# FPGA_DDR3_IO.net
KiCad netlist of a schematic drawn in Altium Designer
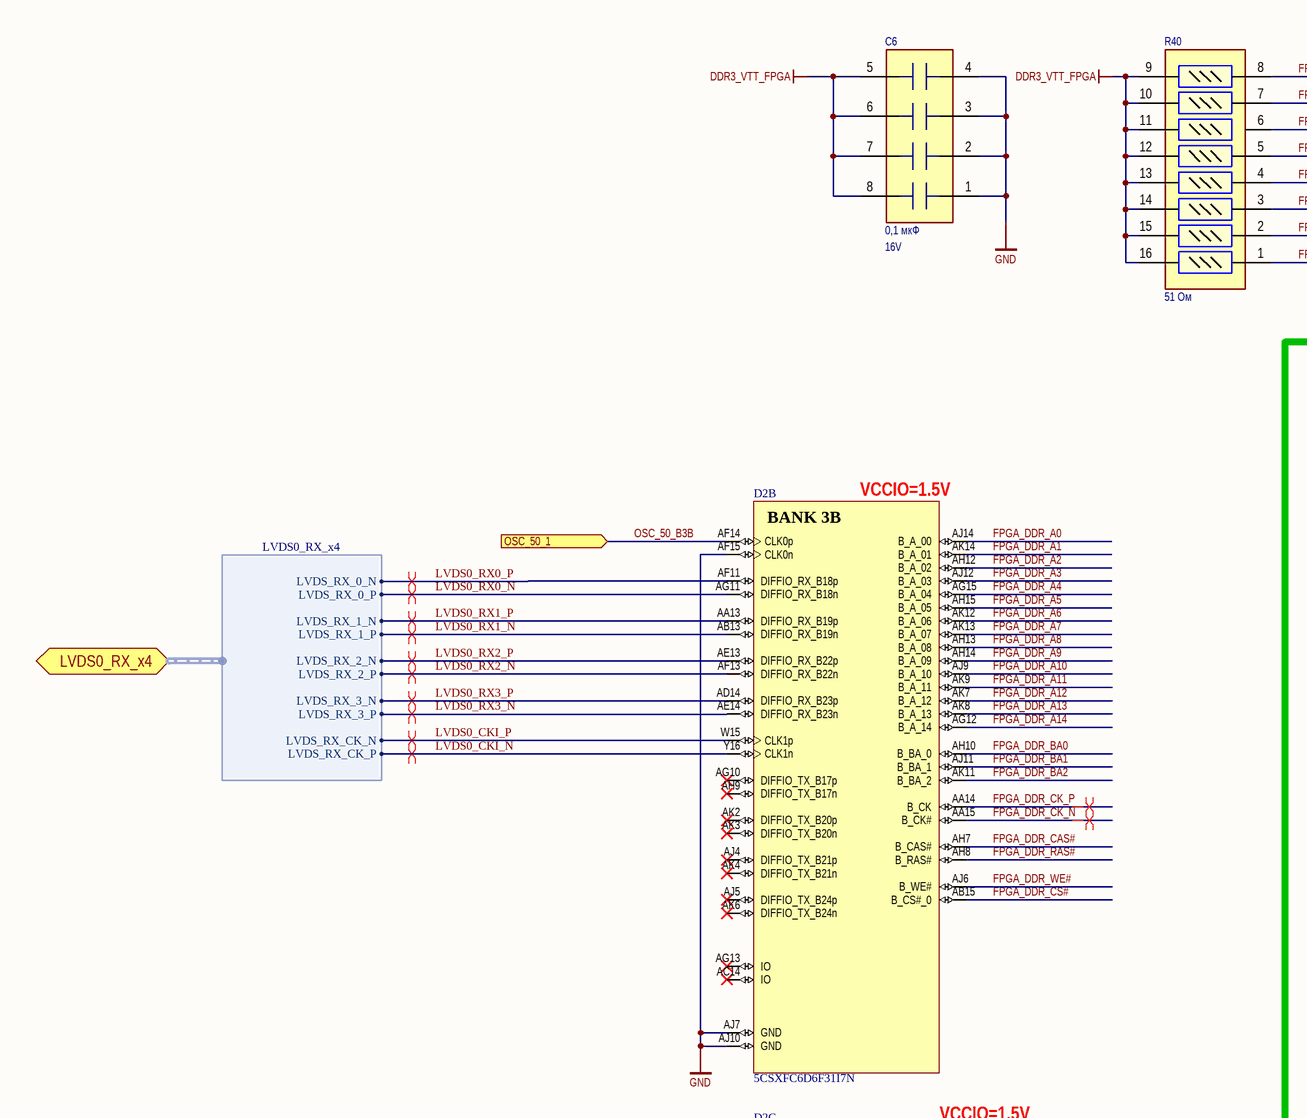
[diagram p0: FPGA_DDR3&IO.SchDoc, top left]
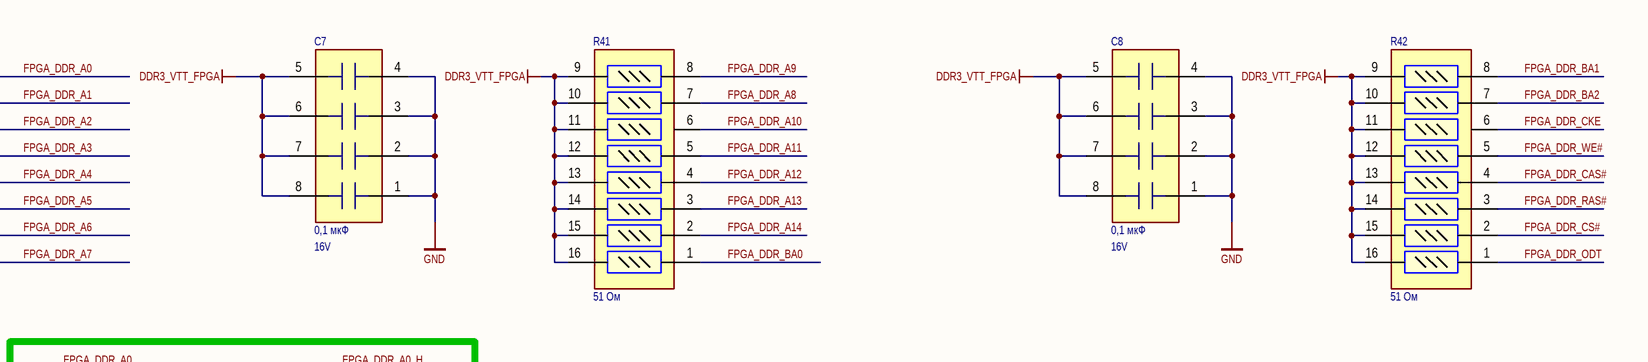
[diagram p1: FPGA_DDR3&IO.SchDoc, top right]
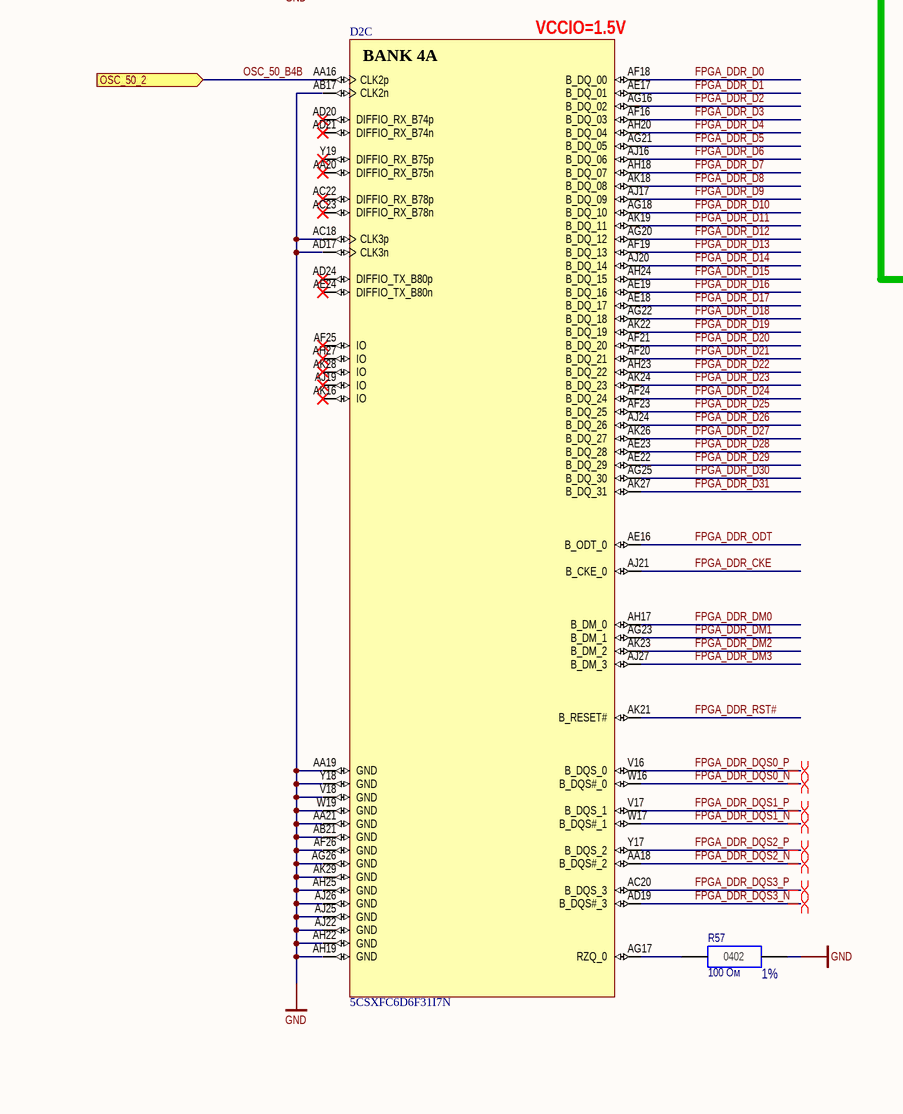
[diagram p2: FPGA_DDR3&IO.SchDoc, bottom left]
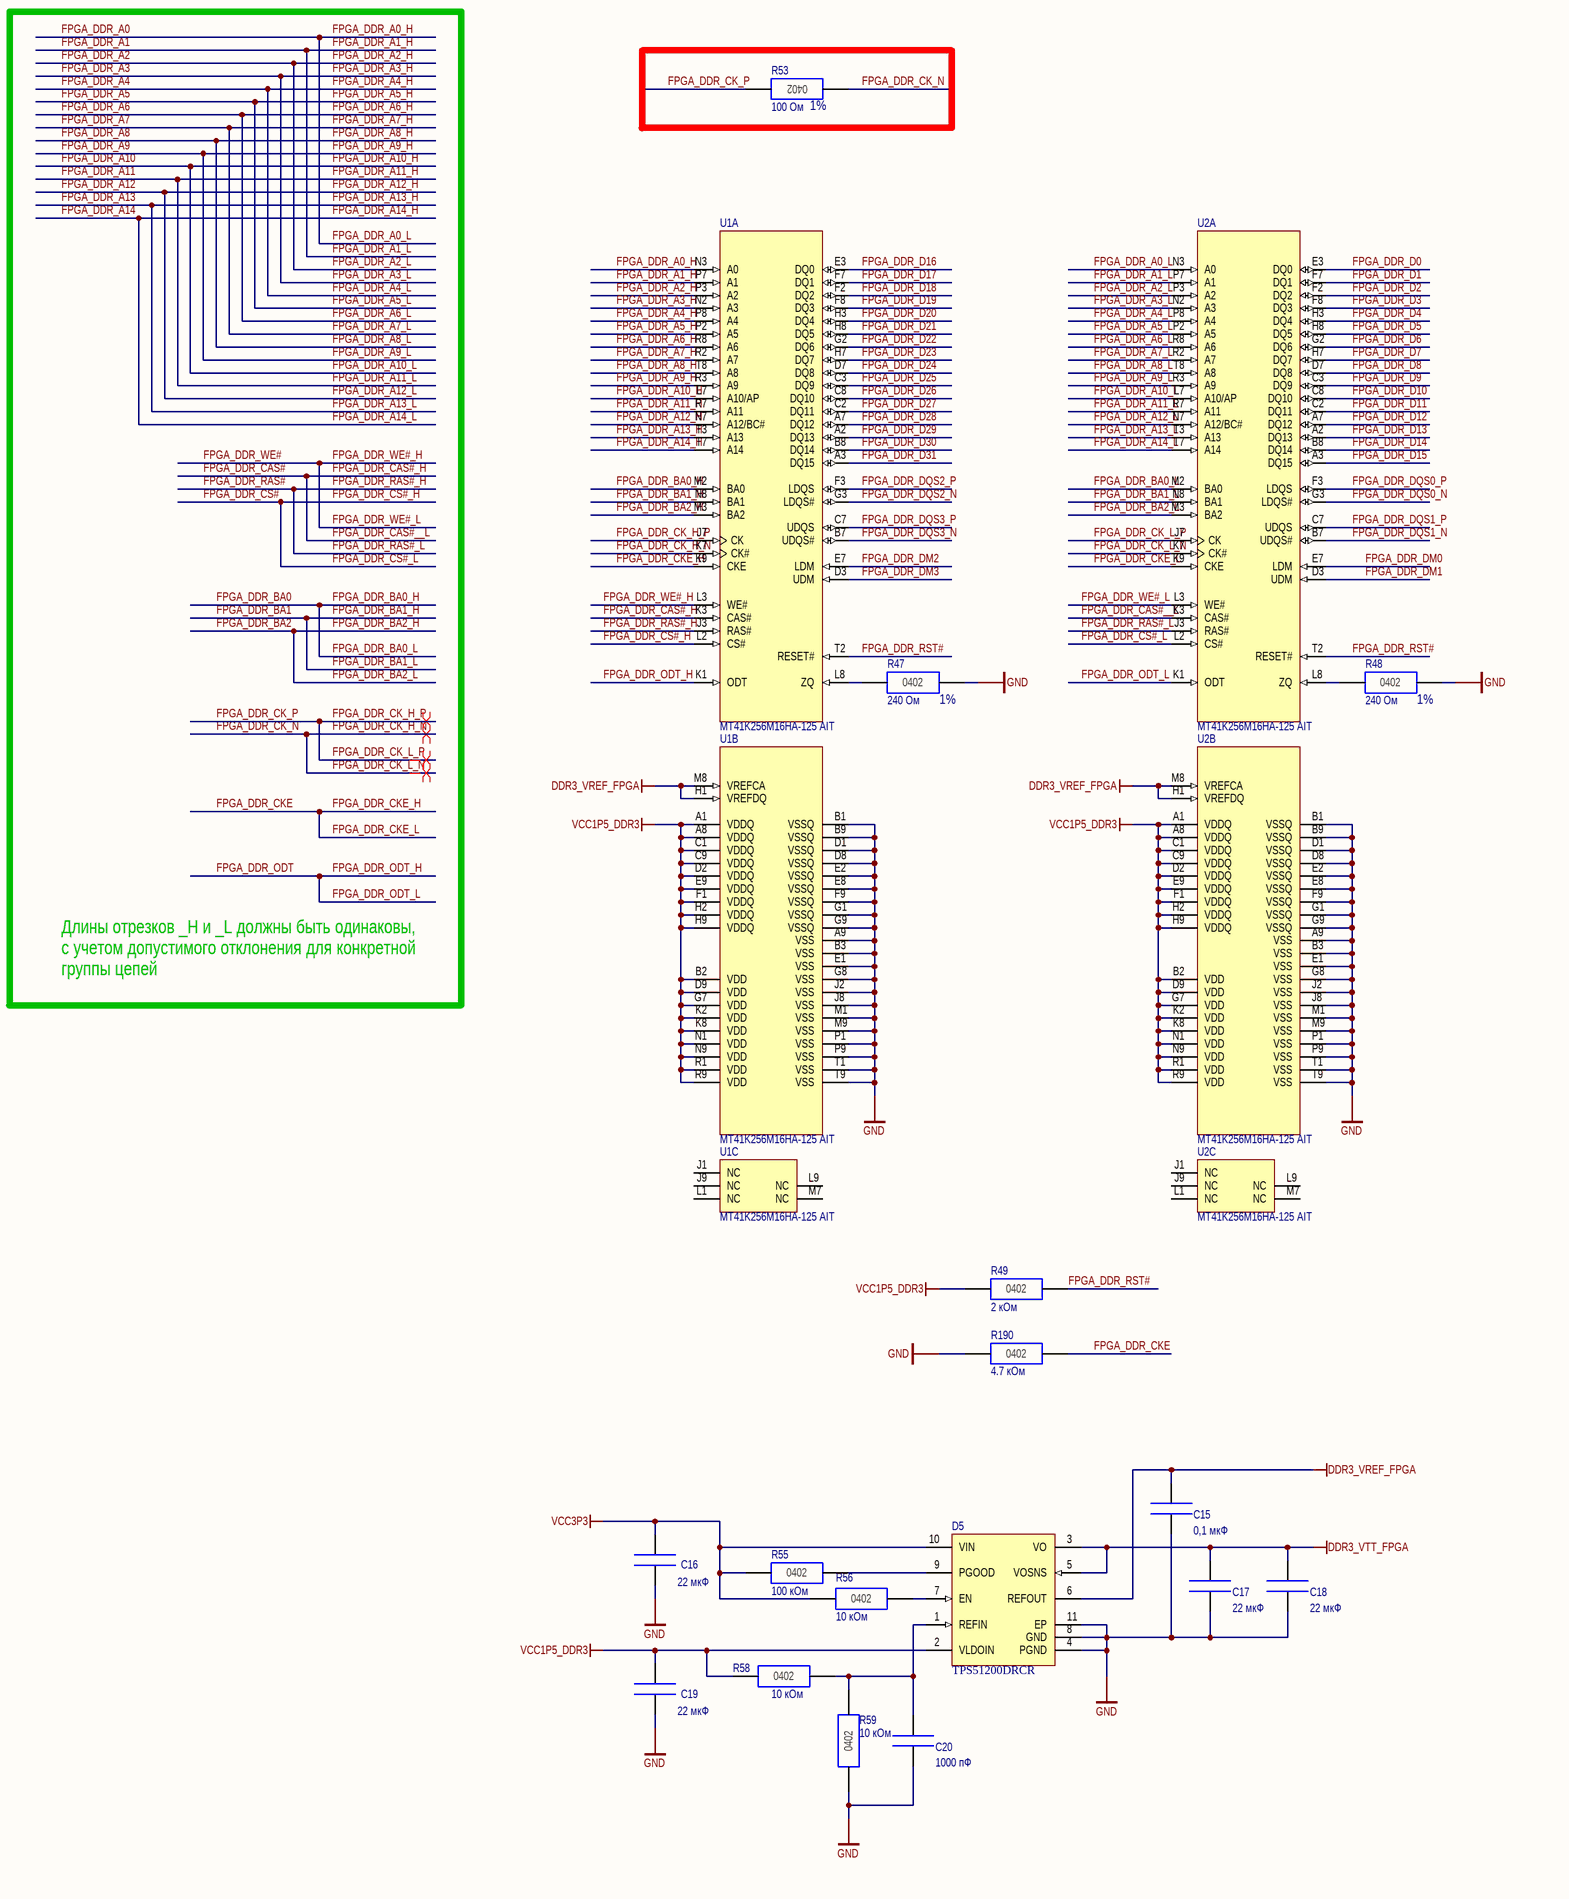
[diagram p3: FPGA_DDR3&IO.SchDoc, bottom right]

(export (version "E")
  (design (tool "Eeschema 10.0.6"))
  (components
    (comp (ref "C6")
      (value "0,1 мкФ")
      (footprint "CAF-80P319X159-8N")
      (description "Чип конденсатор керамический")
      (fields (field (name "V") "16V") (field (name "Comment") "W3A4YC104KAT2A"))
      (libsource (lib "SD_IC") (part "W3A4YC104KAT2A"))
    )
    (comp (ref "C7")
      (value "0,1 мкФ")
      (footprint "CAF-80P319X159-8N")
      (description "Чип конденсатор керамический")
      (fields (field (name "V") "16V") (field (name "Comment") "W3A4YC104KAT2A"))
      (libsource (lib "SD_IC") (part "W3A4YC104KAT2A"))
    )
    (comp (ref "C8")
      (value "0,1 мкФ")
      (footprint "CAF-80P319X159-8N")
      (description "Чип конденсатор керамический")
      (fields (field (name "V") "16V") (field (name "Comment") "W3A4YC104KAT2A"))
      (libsource (lib "SD_IC") (part "W3A4YC104KAT2A"))
    )
    (comp (ref "C15")
      (value "0,1 мкФ")
      (footprint "CC0402(1005)")
      (description "Чип конденсатор керамический")
      (fields (field (name "Comment") "CC0402-X7R-0,1 мкФ-20%-10В"))
      (libsource (lib "Чип конденсаторы") (part "CC0402-X7R-#-20%-10В"))
    )
    (comp (ref "C16")
      (value "22 мкФ")
      (footprint "CC0402(1005)")
      (description "Чип конденсатор керамический")
      (fields (field (name "Comment") "CC0402-X5R-22 мкФ-20%-6.3В"))
      (libsource (lib "Чип конденсаторы") (part "CC0402-X7R-#-20%-10В"))
    )
    (comp (ref "C17")
      (value "22 мкФ")
      (footprint "CC0402(1005)")
      (description "Чип конденсатор керамический")
      (fields (field (name "Comment") "CC0402-X5R-22 мкФ-20%-6.3В"))
      (libsource (lib "Чип конденсаторы") (part "CC0402-X7R-#-20%-10В"))
    )
    (comp (ref "C18")
      (value "22 мкФ")
      (footprint "CC0402(1005)")
      (description "Чип конденсатор керамический")
      (fields (field (name "Comment") "CC0402-X5R-22 мкФ-20%-6.3В"))
      (libsource (lib "Чип конденсаторы") (part "CC0402-X7R-#-20%-10В"))
    )
    (comp (ref "C19")
      (value "22 мкФ")
      (footprint "CC0402(1005)")
      (description "Чип конденсатор керамический")
      (fields (field (name "Comment") "CC0402-X5R-22 мкФ-20%-6.3В"))
      (libsource (lib "Чип конденсаторы") (part "CC0402-X7R-#-20%-10В"))
    )
    (comp (ref "C20")
      (value "1000 пФ")
      (footprint "CC0402(1005)")
      (description "Чип конденсатор керамический")
      (fields (field (name "Comment") "CC0402-NP01000 пФ-1%-50В"))
      (libsource (lib "Чип конденсаторы") (part "CC0402-X7R-#-20%-10В"))
    )
    (comp (ref "D2")
      (value "5CSXFC6D6F31I7N")
      (footprint "ALTR-FBGA896_A-200")
      (fields (field (name "MANUFACTURER") "Altera"))
      (libsource (lib "") (part "5CSXFC6D6F31I7N_1"))
    )
    (comp (ref "D5")
      (value "TPS51200DRCR")
      (footprint "TI-DRC10-2400X1650TP_V")
      (fields (field (name "MANUFACTURER") "Texas Instruments"))
      (libsource (lib "SD_IC") (part "TPS51200DRCR"))
    )
    (comp (ref "R40")
      (value "51 Ом")
      (footprint "CAT16-J8")
      (description "Набор чип резисторов")
      (fields (field (name "Comment") "YC248-JR-07-51 Ом"))
      (libsource (lib "SD_IC") (part "YC248-JR-07-#"))
    )
    (comp (ref "R41")
      (value "51 Ом")
      (footprint "CAT16-J8")
      (description "Набор чип резисторов")
      (fields (field (name "Comment") "YC248-JR-07-51 Ом"))
      (libsource (lib "SD_IC") (part "YC248-JR-07-#"))
    )
    (comp (ref "R42")
      (value "51 Ом")
      (footprint "CAT16-J8")
      (description "Набор чип резисторов")
      (fields (field (name "Comment") "YC248-JR-07-51 Ом"))
      (libsource (lib "SD_IC") (part "YC248-JR-07-#"))
    )
    (comp (ref "R47")
      (value "240 Ом")
      (footprint "CR0402(1005)")
      (description "Чип резистор")
      (fields (field (name "TOLERANCE") "1%") (field (name "Comment") "CR0402-240 Ом-±TOLERANCE"))
      (libsource (lib "") (part "CR0402-#-±5%_1"))
    )
    (comp (ref "R48")
      (value "240 Ом")
      (footprint "CR0402(1005)")
      (description "Чип резистор")
      (fields (field (name "TOLERANCE") "1%") (field (name "Comment") "CR0402-240 Ом-±TOLERANCE"))
      (libsource (lib "") (part "CR0402-#-±5%_1"))
    )
    (comp (ref "R49")
      (value "2 кОм")
      (footprint "CR0402(1005)")
      (description "Чип резистор")
      (fields (field (name "TOLERANCE") "5%") (field (name "Comment") "CR0402-2 кОм-±5%"))
      (libsource (lib "") (part "CR0402-#-±5%_1"))
    )
    (comp (ref "R53")
      (value "100 Ом")
      (footprint "CR0402(1005)")
      (description "Чип резистор")
      (fields (field (name "TOLERANCE") "1%") (field (name "Comment") "CR0402-100 Ом-±TOLERANCE"))
      (libsource (lib "Резисторы") (part "CR0402-#-±5%"))
    )
    (comp (ref "R55")
      (value "100 кОм")
      (footprint "CR0402(1005)")
      (description "Чип резистор")
      (fields (field (name "TOLERANCE") "5%") (field (name "Comment") "CR0402-100 кОм-±5%"))
      (libsource (lib "") (part "CR0402-#-±5%_1"))
    )
    (comp (ref "R56")
      (value "10 кОм")
      (footprint "CR0402(1005)")
      (description "Чип резистор")
      (fields (field (name "TOLERANCE") "5%") (field (name "Comment") "CR0402-10 кОм-±5%"))
      (libsource (lib "") (part "CR0402-#-±5%_1"))
    )
    (comp (ref "R57")
      (value "100 Ом")
      (footprint "CR0402(1005)")
      (description "Чип резистор")
      (fields (field (name "TOLERANCE") "1%") (field (name "Comment") "CR0402-100 Ом-±TOLERANCE"))
      (libsource (lib "") (part "CR0402-#-±5%_1"))
    )
    (comp (ref "R58")
      (value "10 кОм")
      (footprint "CR0402(1005)")
      (description "Чип резистор")
      (fields (field (name "TOLERANCE") "5%") (field (name "Comment") "CR0402-10 кОм-±5%"))
      (libsource (lib "") (part "CR0402-#-±5%_1"))
    )
    (comp (ref "R59")
      (value "10 кОм")
      (footprint "CR0402(1005)")
      (description "Чип резистор")
      (fields (field (name "TOLERANCE") "5%") (field (name "Comment") "CR0402-10 кОм-±5%"))
      (libsource (lib "") (part "CR0402-#-±5%_2"))
    )
    (comp (ref "R190")
      (value "4.7 кОм")
      (footprint "CR0402(1005)")
      (description "Чип резистор")
      (fields (field (name "TOLERANCE") "5%") (field (name "Comment") "CR0402-4.7 кОм-±5%"))
      (libsource (lib "") (part "CR0402-#-±5%_1"))
    )
    (comp (ref "U1")
      (value "MT41K256M16HA-125 AIT")
      (footprint "MICT-HA-96")
      (description "4Gb DDR3-1600 SDRAM, 256Mb x 16, 1.25ns, 1.35V, -40 to 95 degC, 96-Ball FBGA, Pb-Free")
      (fields (field (name "VOLTAGE") "1.35V ") (field (name "MANUFACTURER") "Micron"))
      (libsource (lib "SD_IC") (part "MT41K256M16HA-125 AIT"))
    )
    (comp (ref "U2")
      (value "MT41K256M16HA-125 AIT")
      (footprint "MICT-HA-96")
      (description "4Gb DDR3-1600 SDRAM, 256Mb x 16, 1.25ns, 1.35V, -40 to 95 degC, 96-Ball FBGA, Pb-Free")
      (fields (field (name "VOLTAGE") "1.35V ") (field (name "MANUFACTURER") "Micron"))
      (libsource (lib "SD_IC") (part "MT41K256M16HA-125 AIT"))
    )
  )
  (nets
    (net (code "2") (name "/FPGA_DDR_A0") (class "Default")
      (node (ref "D2") (pin "AJ14") (pinfunction "B_A_00_AJ14") (pintype "bidirectional"))
      (node (ref "R40") (pin "8") (pintype "passive"))
      (node (ref "U1") (pin "N3") (pinfunction "A0_N3") (pintype "input"))
      (node (ref "U2") (pin "N3") (pinfunction "A0_N3") (pintype "input"))
    )
    (net (code "3") (name "/FPGA_DDR_A1") (class "Default")
      (node (ref "D2") (pin "AK14") (pinfunction "B_A_01_AK14") (pintype "bidirectional"))
      (node (ref "R40") (pin "7") (pintype "passive"))
      (node (ref "U1") (pin "P7") (pinfunction "A1_P7") (pintype "input"))
      (node (ref "U2") (pin "P7") (pinfunction "A1_P7") (pintype "input"))
    )
    (net (code "4") (name "/FPGA_DDR_A2") (class "Default")
      (node (ref "D2") (pin "AH12") (pinfunction "B_A_02_AH12") (pintype "bidirectional"))
      (node (ref "R40") (pin "6") (pintype "passive"))
      (node (ref "U1") (pin "P3") (pinfunction "A2_P3") (pintype "input"))
      (node (ref "U2") (pin "P3") (pinfunction "A2_P3") (pintype "input"))
    )
    (net (code "5") (name "/FPGA_DDR_A3") (class "Default")
      (node (ref "D2") (pin "AJ12") (pinfunction "B_A_03_AJ12") (pintype "bidirectional"))
      (node (ref "R40") (pin "5") (pintype "passive"))
      (node (ref "U1") (pin "N2") (pinfunction "A3_N2") (pintype "input"))
      (node (ref "U2") (pin "N2") (pinfunction "A3_N2") (pintype "input"))
    )
    (net (code "6") (name "/FPGA_DDR_A4") (class "Default")
      (node (ref "D2") (pin "AG15") (pinfunction "B_A_04_AG15") (pintype "bidirectional"))
      (node (ref "R40") (pin "4") (pintype "passive"))
      (node (ref "U1") (pin "P8") (pinfunction "A4_P8") (pintype "input"))
      (node (ref "U2") (pin "P8") (pinfunction "A4_P8") (pintype "input"))
    )
    (net (code "7") (name "/FPGA_DDR_A5") (class "Default")
      (node (ref "D2") (pin "AH15") (pinfunction "B_A_05_AH15") (pintype "bidirectional"))
      (node (ref "R40") (pin "3") (pintype "passive"))
      (node (ref "U1") (pin "P2") (pinfunction "A5_P2") (pintype "input"))
      (node (ref "U2") (pin "P2") (pinfunction "A5_P2") (pintype "input"))
    )
    (net (code "8") (name "/FPGA_DDR_A6") (class "Default")
      (node (ref "D2") (pin "AK12") (pinfunction "B_A_06_AK12") (pintype "bidirectional"))
      (node (ref "R40") (pin "2") (pintype "passive"))
      (node (ref "U1") (pin "R8") (pinfunction "A6_R8") (pintype "input"))
      (node (ref "U2") (pin "R8") (pinfunction "A6_R8") (pintype "input"))
    )
    (net (code "9") (name "/FPGA_DDR_A7") (class "Default")
      (node (ref "D2") (pin "AK13") (pinfunction "B_A_07_AK13") (pintype "bidirectional"))
      (node (ref "R40") (pin "1") (pintype "passive"))
      (node (ref "U1") (pin "R2") (pinfunction "A7_R2") (pintype "input"))
      (node (ref "U2") (pin "R2") (pinfunction "A7_R2") (pintype "input"))
    )
    (net (code "10") (name "/FPGA_DDR_A8") (class "Default")
      (node (ref "D2") (pin "AH13") (pinfunction "B_A_08_AH13") (pintype "bidirectional"))
      (node (ref "R41") (pin "7") (pintype "passive"))
      (node (ref "U1") (pin "T8") (pinfunction "A8_T8") (pintype "input"))
      (node (ref "U2") (pin "T8") (pinfunction "A8_T8") (pintype "input"))
    )
    (net (code "11") (name "/FPGA_DDR_A9") (class "Default")
      (node (ref "D2") (pin "AH14") (pinfunction "B_A_09_AH14") (pintype "bidirectional"))
      (node (ref "R41") (pin "8") (pintype "passive"))
      (node (ref "U1") (pin "R3") (pinfunction "A9_R3") (pintype "input"))
      (node (ref "U2") (pin "R3") (pinfunction "A9_R3") (pintype "input"))
    )
    (net (code "12") (name "/FPGA_DDR_A10") (class "Default")
      (node (ref "D2") (pin "AJ9") (pinfunction "B_A_10_AJ9") (pintype "bidirectional"))
      (node (ref "R41") (pin "6") (pintype "passive"))
      (node (ref "U1") (pin "L7") (pinfunction "A10/AP_L7") (pintype "input"))
      (node (ref "U2") (pin "L7") (pinfunction "A10/AP_L7") (pintype "input"))
    )
    (net (code "13") (name "/FPGA_DDR_A11") (class "Default")
      (node (ref "D2") (pin "AK9") (pinfunction "B_A_11_AK9") (pintype "bidirectional"))
      (node (ref "R41") (pin "5") (pintype "passive"))
      (node (ref "U1") (pin "R7") (pinfunction "A11_R7") (pintype "input"))
      (node (ref "U2") (pin "R7") (pinfunction "A11_R7") (pintype "input"))
    )
    (net (code "14") (name "/FPGA_DDR_A12") (class "Default")
      (node (ref "D2") (pin "AK7") (pinfunction "B_A_12_AK7") (pintype "bidirectional"))
      (node (ref "R41") (pin "4") (pintype "passive"))
      (node (ref "U1") (pin "N7") (pinfunction "A12/BC#_N7") (pintype "input"))
      (node (ref "U2") (pin "N7") (pinfunction "A12/BC#_N7") (pintype "input"))
    )
    (net (code "15") (name "/FPGA_DDR_A13") (class "Default")
      (node (ref "D2") (pin "AK8") (pinfunction "B_A_13_AK8") (pintype "bidirectional"))
      (node (ref "R41") (pin "3") (pintype "passive"))
      (node (ref "U1") (pin "T3") (pinfunction "A13_T3") (pintype "input"))
      (node (ref "U2") (pin "T3") (pinfunction "A13_T3") (pintype "input"))
    )
    (net (code "16") (name "/FPGA_DDR_A14") (class "Default")
      (node (ref "D2") (pin "AG12") (pinfunction "B_A_14_AG12") (pintype "bidirectional"))
      (node (ref "R41") (pin "2") (pintype "passive"))
      (node (ref "U1") (pin "T7") (pinfunction "A14_T7") (pintype "input"))
      (node (ref "U2") (pin "T7") (pinfunction "A14_T7") (pintype "input"))
    )
    (net (code "17") (name "/FPGA_DDR_BA0") (class "Default")
      (node (ref "D2") (pin "AH10") (pinfunction "B_BA_0_AH10") (pintype "bidirectional"))
      (node (ref "R41") (pin "1") (pintype "passive"))
      (node (ref "U1") (pin "M2") (pinfunction "BA0_M2") (pintype "input"))
      (node (ref "U2") (pin "M2") (pinfunction "BA0_M2") (pintype "input"))
    )
    (net (code "18") (name "/FPGA_DDR_BA1") (class "Default")
      (node (ref "D2") (pin "AJ11") (pinfunction "B_BA_1_AJ11") (pintype "bidirectional"))
      (node (ref "R42") (pin "8") (pintype "passive"))
      (node (ref "U1") (pin "N8") (pinfunction "BA1_N8") (pintype "input"))
      (node (ref "U2") (pin "N8") (pinfunction "BA1_N8") (pintype "input"))
    )
    (net (code "19") (name "/FPGA_DDR_BA2") (class "Default")
      (node (ref "D2") (pin "AK11") (pinfunction "B_BA_2_AK11") (pintype "bidirectional"))
      (node (ref "R42") (pin "7") (pintype "passive"))
      (node (ref "U1") (pin "M3") (pinfunction "BA2_M3") (pintype "input"))
      (node (ref "U2") (pin "M3") (pinfunction "BA2_M3") (pintype "input"))
    )
    (net (code "20") (name "/FPGA_DDR_CAS#") (class "Default")
      (node (ref "D2") (pin "AH7") (pinfunction "B_CAS#_AH7") (pintype "bidirectional"))
      (node (ref "R42") (pin "4") (pintype "passive"))
      (node (ref "U1") (pin "K3") (pinfunction "CAS#_K3") (pintype "input"))
      (node (ref "U2") (pin "K3") (pinfunction "CAS#_K3") (pintype "input"))
    )
    (net (code "21") (name "/FPGA_DDR_CKE") (class "Default")
      (node (ref "D2") (pin "AJ21") (pinfunction "B_CKE_0_AJ21") (pintype "bidirectional"))
      (node (ref "R190") (pin "2") (pinfunction "-_2") (pintype "passive"))
      (node (ref "R42") (pin "6") (pintype "passive"))
      (node (ref "U1") (pin "K9") (pinfunction "CKE_K9") (pintype "input"))
      (node (ref "U2") (pin "K9") (pinfunction "CKE_K9") (pintype "input"))
    )
    (net (code "22") (name "/FPGA_DDR_CK_H_N") (class "Default")
      (node (ref "D2") (pin "AA15") (pinfunction "B_CK#_AA15") (pintype "bidirectional"))
      (node (ref "R53") (pin "1") (pinfunction "+_1") (pintype "passive"))
      (node (ref "U1") (pin "K7") (pinfunction "CK#_K7") (pintype "input"))
      (node (ref "U2") (pin "K7") (pinfunction "CK#_K7") (pintype "input"))
    )
    (net (code "23") (name "/FPGA_DDR_CK_H_P") (class "Default")
      (node (ref "D2") (pin "AA14") (pinfunction "B_CK_AA14") (pintype "bidirectional"))
      (node (ref "R53") (pin "2") (pinfunction "-_2") (pintype "passive"))
      (node (ref "U1") (pin "J7") (pinfunction "CK_J7") (pintype "input"))
      (node (ref "U2") (pin "J7") (pinfunction "CK_J7") (pintype "input"))
    )
    (net (code "24") (name "/FPGA_DDR_CS#") (class "Default")
      (node (ref "D2") (pin "AB15") (pinfunction "B_CS#_0_AB15") (pintype "bidirectional"))
      (node (ref "R42") (pin "2") (pintype "passive"))
      (node (ref "U1") (pin "L2") (pinfunction "CS#_L2") (pintype "input"))
      (node (ref "U2") (pin "L2") (pinfunction "CS#_L2") (pintype "input"))
    )
    (net (code "25") (name "/FPGA_DDR_D0") (class "Default")
      (node (ref "D2") (pin "AF18") (pinfunction "B_DQ_00_AF18") (pintype "bidirectional"))
      (node (ref "U2") (pin "E3") (pinfunction "DQ0_E3") (pintype "bidirectional"))
    )
    (net (code "26") (name "/FPGA_DDR_D1") (class "Default")
      (node (ref "D2") (pin "AE17") (pinfunction "B_DQ_01_AE17") (pintype "bidirectional"))
      (node (ref "U2") (pin "F7") (pinfunction "DQ1_F7") (pintype "bidirectional"))
    )
    (net (code "27") (name "/FPGA_DDR_D2") (class "Default")
      (node (ref "D2") (pin "AG16") (pinfunction "B_DQ_02_AG16") (pintype "bidirectional"))
      (node (ref "U2") (pin "F2") (pinfunction "DQ2_F2") (pintype "bidirectional"))
    )
    (net (code "28") (name "/FPGA_DDR_D3") (class "Default")
      (node (ref "D2") (pin "AF16") (pinfunction "B_DQ_03_AF16") (pintype "bidirectional"))
      (node (ref "U2") (pin "F8") (pinfunction "DQ3_F8") (pintype "bidirectional"))
    )
    (net (code "29") (name "/FPGA_DDR_D4") (class "Default")
      (node (ref "D2") (pin "AH20") (pinfunction "B_DQ_04_AH20") (pintype "bidirectional"))
      (node (ref "U2") (pin "H3") (pinfunction "DQ4_H3") (pintype "bidirectional"))
    )
    (net (code "30") (name "/FPGA_DDR_D5") (class "Default")
      (node (ref "D2") (pin "AG21") (pinfunction "B_DQ_05_AG21") (pintype "bidirectional"))
      (node (ref "U2") (pin "H8") (pinfunction "DQ5_H8") (pintype "bidirectional"))
    )
    (net (code "31") (name "/FPGA_DDR_D6") (class "Default")
      (node (ref "D2") (pin "AJ16") (pinfunction "B_DQ_06_AJ16") (pintype "bidirectional"))
      (node (ref "U2") (pin "G2") (pinfunction "DQ6_G2") (pintype "bidirectional"))
    )
    (net (code "32") (name "/FPGA_DDR_D7") (class "Default")
      (node (ref "D2") (pin "AH18") (pinfunction "B_DQ_07_AH18") (pintype "bidirectional"))
      (node (ref "U2") (pin "H7") (pinfunction "DQ7_H7") (pintype "bidirectional"))
    )
    (net (code "33") (name "/FPGA_DDR_D8") (class "Default")
      (node (ref "D2") (pin "AK18") (pinfunction "B_DQ_08_AK18") (pintype "bidirectional"))
      (node (ref "U2") (pin "D7") (pinfunction "DQ8_D7") (pintype "bidirectional"))
    )
    (net (code "34") (name "/FPGA_DDR_D9") (class "Default")
      (node (ref "D2") (pin "AJ17") (pinfunction "B_DQ_09_AJ17") (pintype "bidirectional"))
      (node (ref "U2") (pin "C3") (pinfunction "DQ9_C3") (pintype "bidirectional"))
    )
    (net (code "35") (name "/FPGA_DDR_D10") (class "Default")
      (node (ref "D2") (pin "AG18") (pinfunction "B_DQ_10_AG18") (pintype "bidirectional"))
      (node (ref "U2") (pin "C8") (pinfunction "DQ10_C8") (pintype "bidirectional"))
    )
    (net (code "36") (name "/FPGA_DDR_D11") (class "Default")
      (node (ref "D2") (pin "AK19") (pinfunction "B_DQ_11_AK19") (pintype "bidirectional"))
      (node (ref "U2") (pin "C2") (pinfunction "DQ11_C2") (pintype "bidirectional"))
    )
    (net (code "37") (name "/FPGA_DDR_D12") (class "Default")
      (node (ref "D2") (pin "AG20") (pinfunction "B_DQ_12_AG20") (pintype "bidirectional"))
      (node (ref "U2") (pin "A7") (pinfunction "DQ12_A7") (pintype "bidirectional"))
    )
    (net (code "38") (name "/FPGA_DDR_D13") (class "Default")
      (node (ref "D2") (pin "AF19") (pinfunction "B_DQ_13_AF19") (pintype "bidirectional"))
      (node (ref "U2") (pin "A2") (pinfunction "DQ13_A2") (pintype "bidirectional"))
    )
    (net (code "39") (name "/FPGA_DDR_D14") (class "Default")
      (node (ref "D2") (pin "AJ20") (pinfunction "B_DQ_14_AJ20") (pintype "bidirectional"))
      (node (ref "U2") (pin "B8") (pinfunction "DQ14_B8") (pintype "bidirectional"))
    )
    (net (code "40") (name "/FPGA_DDR_D15") (class "Default")
      (node (ref "D2") (pin "AH24") (pinfunction "B_DQ_15_AH24") (pintype "bidirectional"))
      (node (ref "U2") (pin "A3") (pinfunction "DQ15_A3") (pintype "bidirectional"))
    )
    (net (code "41") (name "/FPGA_DDR_D16") (class "Default")
      (node (ref "D2") (pin "AE19") (pinfunction "B_DQ_16_AE19") (pintype "bidirectional"))
      (node (ref "U1") (pin "E3") (pinfunction "DQ0_E3") (pintype "bidirectional"))
    )
    (net (code "42") (name "/FPGA_DDR_D17") (class "Default")
      (node (ref "D2") (pin "AE18") (pinfunction "B_DQ_17_AE18") (pintype "bidirectional"))
      (node (ref "U1") (pin "F7") (pinfunction "DQ1_F7") (pintype "bidirectional"))
    )
    (net (code "43") (name "/FPGA_DDR_D18") (class "Default")
      (node (ref "D2") (pin "AG22") (pinfunction "B_DQ_18_AG22") (pintype "bidirectional"))
      (node (ref "U1") (pin "F2") (pinfunction "DQ2_F2") (pintype "bidirectional"))
    )
    (net (code "44") (name "/FPGA_DDR_D19") (class "Default")
      (node (ref "D2") (pin "AK22") (pinfunction "B_DQ_19_AK22") (pintype "bidirectional"))
      (node (ref "U1") (pin "F8") (pinfunction "DQ3_F8") (pintype "bidirectional"))
    )
    (net (code "45") (name "/FPGA_DDR_D20") (class "Default")
      (node (ref "D2") (pin "AF21") (pinfunction "B_DQ_20_AF21") (pintype "bidirectional"))
      (node (ref "U1") (pin "H3") (pinfunction "DQ4_H3") (pintype "bidirectional"))
    )
    (net (code "46") (name "/FPGA_DDR_D21") (class "Default")
      (node (ref "D2") (pin "AF20") (pinfunction "B_DQ_21_AF20") (pintype "bidirectional"))
      (node (ref "U1") (pin "H8") (pinfunction "DQ5_H8") (pintype "bidirectional"))
    )
    (net (code "47") (name "/FPGA_DDR_D22") (class "Default")
      (node (ref "D2") (pin "AH23") (pinfunction "B_DQ_22_AH23") (pintype "bidirectional"))
      (node (ref "U1") (pin "G2") (pinfunction "DQ6_G2") (pintype "bidirectional"))
    )
    (net (code "48") (name "/FPGA_DDR_D23") (class "Default")
      (node (ref "D2") (pin "AK24") (pinfunction "B_DQ_23_AK24") (pintype "bidirectional"))
      (node (ref "U1") (pin "H7") (pinfunction "DQ7_H7") (pintype "bidirectional"))
    )
    (net (code "49") (name "/FPGA_DDR_D24") (class "Default")
      (node (ref "D2") (pin "AF24") (pinfunction "B_DQ_24_AF24") (pintype "bidirectional"))
      (node (ref "U1") (pin "D7") (pinfunction "DQ8_D7") (pintype "bidirectional"))
    )
    (net (code "50") (name "/FPGA_DDR_D25") (class "Default")
      (node (ref "D2") (pin "AF23") (pinfunction "B_DQ_25_AF23") (pintype "bidirectional"))
      (node (ref "U1") (pin "C3") (pinfunction "DQ9_C3") (pintype "bidirectional"))
    )
    (net (code "51") (name "/FPGA_DDR_D26") (class "Default")
      (node (ref "D2") (pin "AJ24") (pinfunction "B_DQ_26_AJ24") (pintype "bidirectional"))
      (node (ref "U1") (pin "C8") (pinfunction "DQ10_C8") (pintype "bidirectional"))
    )
    (net (code "52") (name "/FPGA_DDR_D27") (class "Default")
      (node (ref "D2") (pin "AK26") (pinfunction "B_DQ_27_AK26") (pintype "bidirectional"))
      (node (ref "U1") (pin "C2") (pinfunction "DQ11_C2") (pintype "bidirectional"))
    )
    (net (code "53") (name "/FPGA_DDR_D28") (class "Default")
      (node (ref "D2") (pin "AE23") (pinfunction "B_DQ_28_AE23") (pintype "bidirectional"))
      (node (ref "U1") (pin "A7") (pinfunction "DQ12_A7") (pintype "bidirectional"))
    )
    (net (code "54") (name "/FPGA_DDR_D29") (class "Default")
      (node (ref "D2") (pin "AE22") (pinfunction "B_DQ_29_AE22") (pintype "bidirectional"))
      (node (ref "U1") (pin "A2") (pinfunction "DQ13_A2") (pintype "bidirectional"))
    )
    (net (code "55") (name "/FPGA_DDR_D30") (class "Default")
      (node (ref "D2") (pin "AG25") (pinfunction "B_DQ_30_AG25") (pintype "bidirectional"))
      (node (ref "U1") (pin "B8") (pinfunction "DQ14_B8") (pintype "bidirectional"))
    )
    (net (code "56") (name "/FPGA_DDR_D31") (class "Default")
      (node (ref "D2") (pin "AK27") (pinfunction "B_DQ_31_AK27") (pintype "bidirectional"))
      (node (ref "U1") (pin "A3") (pinfunction "DQ15_A3") (pintype "bidirectional"))
    )
    (net (code "57") (name "/FPGA_DDR_DM0") (class "Default")
      (node (ref "D2") (pin "AH17") (pinfunction "B_DM_0_AH17") (pintype "bidirectional"))
      (node (ref "U2") (pin "E7") (pinfunction "LDM_E7") (pintype "input"))
    )
    (net (code "58") (name "/FPGA_DDR_DM1") (class "Default")
      (node (ref "D2") (pin "AG23") (pinfunction "B_DM_1_AG23") (pintype "bidirectional"))
      (node (ref "U2") (pin "D3") (pinfunction "UDM_D3") (pintype "input"))
    )
    (net (code "59") (name "/FPGA_DDR_DM2") (class "Default")
      (node (ref "D2") (pin "AK23") (pinfunction "B_DM_2_AK23") (pintype "bidirectional"))
      (node (ref "U1") (pin "E7") (pinfunction "LDM_E7") (pintype "input"))
    )
    (net (code "60") (name "/FPGA_DDR_DM3") (class "Default")
      (node (ref "D2") (pin "AJ27") (pinfunction "B_DM_3_AJ27") (pintype "bidirectional"))
      (node (ref "U1") (pin "D3") (pinfunction "UDM_D3") (pintype "input"))
    )
    (net (code "61") (name "/FPGA_DDR_DQS0_N") (class "Default")
      (node (ref "D2") (pin "W16") (pinfunction "B_DQS#_0_W16") (pintype "bidirectional"))
      (node (ref "U2") (pin "G3") (pinfunction "LDQS#_G3") (pintype "bidirectional"))
    )
    (net (code "62") (name "/FPGA_DDR_DQS0_P") (class "Default")
      (node (ref "D2") (pin "V16") (pinfunction "B_DQS_0_V16") (pintype "bidirectional"))
      (node (ref "U2") (pin "F3") (pinfunction "LDQS_F3") (pintype "bidirectional"))
    )
    (net (code "63") (name "/FPGA_DDR_DQS1_N") (class "Default")
      (node (ref "D2") (pin "W17") (pinfunction "B_DQS#_1_W17") (pintype "bidirectional"))
      (node (ref "U2") (pin "B7") (pinfunction "UDQS#_B7") (pintype "bidirectional"))
    )
    (net (code "64") (name "/FPGA_DDR_DQS1_P") (class "Default")
      (node (ref "D2") (pin "V17") (pinfunction "B_DQS_1_V17") (pintype "bidirectional"))
      (node (ref "U2") (pin "C7") (pinfunction "UDQS_C7") (pintype "bidirectional"))
    )
    (net (code "65") (name "/FPGA_DDR_DQS2_N") (class "Default")
      (node (ref "D2") (pin "AA18") (pinfunction "B_DQS#_2_AA18") (pintype "bidirectional"))
      (node (ref "U1") (pin "G3") (pinfunction "LDQS#_G3") (pintype "bidirectional"))
    )
    (net (code "66") (name "/FPGA_DDR_DQS2_P") (class "Default")
      (node (ref "D2") (pin "Y17") (pinfunction "B_DQS_2_Y17") (pintype "bidirectional"))
      (node (ref "U1") (pin "F3") (pinfunction "LDQS_F3") (pintype "bidirectional"))
    )
    (net (code "67") (name "/FPGA_DDR_DQS3_N") (class "Default")
      (node (ref "D2") (pin "AD19") (pinfunction "B_DQS#_3_AD19") (pintype "bidirectional"))
      (node (ref "U1") (pin "B7") (pinfunction "UDQS#_B7") (pintype "bidirectional"))
    )
    (net (code "68") (name "/FPGA_DDR_DQS3_P") (class "Default")
      (node (ref "D2") (pin "AC20") (pinfunction "B_DQS_3_AC20") (pintype "bidirectional"))
      (node (ref "U1") (pin "C7") (pinfunction "UDQS_C7") (pintype "bidirectional"))
    )
    (net (code "69") (name "/FPGA_DDR_ODT") (class "Default")
      (node (ref "D2") (pin "AE16") (pinfunction "B_ODT_0_AE16") (pintype "bidirectional"))
      (node (ref "R42") (pin "1") (pintype "passive"))
      (node (ref "U1") (pin "K1") (pinfunction "ODT_K1") (pintype "input"))
      (node (ref "U2") (pin "K1") (pinfunction "ODT_K1") (pintype "input"))
    )
    (net (code "70") (name "/FPGA_DDR_RAS#") (class "Default")
      (node (ref "D2") (pin "AH8") (pinfunction "B_RAS#_AH8") (pintype "bidirectional"))
      (node (ref "R42") (pin "3") (pintype "passive"))
      (node (ref "U1") (pin "J3") (pinfunction "RAS#_J3") (pintype "input"))
      (node (ref "U2") (pin "J3") (pinfunction "RAS#_J3") (pintype "input"))
    )
    (net (code "71") (name "/FPGA_DDR_RST#") (class "Default")
      (node (ref "D2") (pin "AK21") (pinfunction "B_RESET#_AK21") (pintype "bidirectional"))
      (node (ref "R49") (pin "2") (pinfunction "-_2") (pintype "passive"))
      (node (ref "U1") (pin "T2") (pinfunction "RESET#_T2") (pintype "input"))
      (node (ref "U2") (pin "T2") (pinfunction "RESET#_T2") (pintype "input"))
    )
    (net (code "72") (name "/FPGA_DDR_WE#") (class "Default")
      (node (ref "D2") (pin "AJ6") (pinfunction "B_WE#_AJ6") (pintype "bidirectional"))
      (node (ref "R42") (pin "5") (pintype "passive"))
      (node (ref "U1") (pin "L3") (pinfunction "WE#_L3") (pintype "input"))
      (node (ref "U2") (pin "L3") (pinfunction "WE#_L3") (pintype "input"))
    )
    (net (code "74") (name "/LVDS0_CKI_P") (class "Default")
      (node (ref "D2") (pin "W15") (pinfunction "CLK1p_W15") (pintype "bidirectional"))
    )
    (net (code "76") (name "/LVDS0_RX0_P") (class "Default")
      (node (ref "D2") (pin "AF11") (pinfunction "DIFFIO_RX_B18p_AF11") (pintype "bidirectional"))
    )
    (net (code "77") (name "/LVDS0_RX1_N") (class "Default")
      (node (ref "D2") (pin "AB13") (pinfunction "DIFFIO_RX_B19n_AB13") (pintype "bidirectional"))
    )
    (net (code "78") (name "/LVDS0_RX1_P") (class "Default")
      (node (ref "D2") (pin "AA13") (pinfunction "DIFFIO_RX_B19p_AA13") (pintype "bidirectional"))
    )
    (net (code "79") (name "/LVDS0_RX2_N") (class "Default")
      (node (ref "D2") (pin "AF13") (pinfunction "DIFFIO_RX_B22n_AF13") (pintype "bidirectional"))
    )
    (net (code "80") (name "/LVDS0_RX2_P") (class "Default")
      (node (ref "D2") (pin "AE13") (pinfunction "DIFFIO_RX_B22p_AE13") (pintype "bidirectional"))
    )
    (net (code "82") (name "/LVDS0_RX3_N") (class "Default")
      (node (ref "D2") (pin "AE14") (pinfunction "DIFFIO_RX_B23n_AE14") (pintype "bidirectional"))
    )
    (net (code "83") (name "/LVDS0_RX3_P") (class "Default")
      (node (ref "D2") (pin "AD14") (pinfunction "DIFFIO_RX_B23p_AD14") (pintype "bidirectional"))
    )
    (net (code "84") (name "/OSC_50_B3B") (class "Default")
      (node (ref "D2") (pin "AF14") (pinfunction "CLK0p_AF14") (pintype "bidirectional"))
    )
    (net (code "86") (name "/OSC_50_B4B") (class "Default")
      (node (ref "D2") (pin "AA16") (pinfunction "CLK2p_AA16") (pintype "bidirectional"))
    )
    (net (code "87") (name "DDR3_VREF_FPGA") (class "Default")
      (node (ref "C15") (pin "1") (pinfunction "+_1") (pintype "passive"))
      (node (ref "D5") (pin "6") (pinfunction "REFOUT_6") (pintype "power_in"))
      (node (ref "U1") (pin "H1") (pinfunction "VREFDQ_H1") (pintype "input"))
      (node (ref "U1") (pin "M8") (pinfunction "VREFCA_M8") (pintype "input"))
      (node (ref "U2") (pin "H1") (pinfunction "VREFDQ_H1") (pintype "input"))
      (node (ref "U2") (pin "M8") (pinfunction "VREFCA_M8") (pintype "input"))
    )
    (net (code "88") (name "DDR3_VTT_FPGA") (class "Default")
      (node (ref "C17") (pin "1") (pinfunction "+_1") (pintype "passive"))
      (node (ref "C18") (pin "1") (pinfunction "+_1") (pintype "passive"))
      (node (ref "C6") (pin "5") (pintype "passive"))
      (node (ref "C6") (pin "6") (pintype "passive"))
      (node (ref "C6") (pin "7") (pintype "passive"))
      (node (ref "C6") (pin "8") (pintype "passive"))
      (node (ref "C7") (pin "5") (pintype "passive"))
      (node (ref "C7") (pin "6") (pintype "passive"))
      (node (ref "C7") (pin "7") (pintype "passive"))
      (node (ref "C7") (pin "8") (pintype "passive"))
      (node (ref "C8") (pin "5") (pintype "passive"))
      (node (ref "C8") (pin "6") (pintype "passive"))
      (node (ref "C8") (pin "7") (pintype "passive"))
      (node (ref "C8") (pin "8") (pintype "passive"))
      (node (ref "D5") (pin "3") (pinfunction "VO_3") (pintype "power_in"))
      (node (ref "D5") (pin "5") (pinfunction "VOSNS_5") (pintype "input"))
      (node (ref "R40") (pin "10") (pintype "passive"))
      (node (ref "R40") (pin "11") (pintype "passive"))
      (node (ref "R40") (pin "12") (pintype "passive"))
      (node (ref "R40") (pin "13") (pintype "passive"))
      (node (ref "R40") (pin "14") (pintype "passive"))
      (node (ref "R40") (pin "15") (pintype "passive"))
      (node (ref "R40") (pin "16") (pintype "passive"))
      (node (ref "R40") (pin "9") (pintype "passive"))
      (node (ref "R41") (pin "10") (pintype "passive"))
      (node (ref "R41") (pin "11") (pintype "passive"))
      (node (ref "R41") (pin "12") (pintype "passive"))
      (node (ref "R41") (pin "13") (pintype "passive"))
      (node (ref "R41") (pin "14") (pintype "passive"))
      (node (ref "R41") (pin "15") (pintype "passive"))
      (node (ref "R41") (pin "16") (pintype "passive"))
      (node (ref "R41") (pin "9") (pintype "passive"))
      (node (ref "R42") (pin "10") (pintype "passive"))
      (node (ref "R42") (pin "11") (pintype "passive"))
      (node (ref "R42") (pin "12") (pintype "passive"))
      (node (ref "R42") (pin "13") (pintype "passive"))
      (node (ref "R42") (pin "14") (pintype "passive"))
      (node (ref "R42") (pin "15") (pintype "passive"))
      (node (ref "R42") (pin "16") (pintype "passive"))
      (node (ref "R42") (pin "9") (pintype "passive"))
    )
    (net (code "89") (name "GND") (class "Default")
      (node (ref "C15") (pin "2") (pinfunction "-_2") (pintype "passive"))
      (node (ref "C16") (pin "2") (pinfunction "-_2") (pintype "passive"))
      (node (ref "C17") (pin "2") (pinfunction "-_2") (pintype "passive"))
      (node (ref "C18") (pin "2") (pinfunction "-_2") (pintype "passive"))
      (node (ref "C19") (pin "2") (pinfunction "-_2") (pintype "passive"))
      (node (ref "C20") (pin "2") (pinfunction "-_2") (pintype "passive"))
      (node (ref "C6") (pin "1") (pintype "passive"))
      (node (ref "C6") (pin "2") (pintype "passive"))
      (node (ref "C6") (pin "3") (pintype "passive"))
      (node (ref "C6") (pin "4") (pintype "passive"))
      (node (ref "C7") (pin "1") (pintype "passive"))
      (node (ref "C7") (pin "2") (pintype "passive"))
      (node (ref "C7") (pin "3") (pintype "passive"))
      (node (ref "C7") (pin "4") (pintype "passive"))
      (node (ref "C8") (pin "1") (pintype "passive"))
      (node (ref "C8") (pin "2") (pintype "passive"))
      (node (ref "C8") (pin "3") (pintype "passive"))
      (node (ref "C8") (pin "4") (pintype "passive"))
      (node (ref "D2") (pin "AF15") (pinfunction "CLK0n_AF15") (pintype "bidirectional"))
      (node (ref "D2") (pin "AJ10") (pinfunction "GND_AJ10") (pintype "bidirectional"))
      (node (ref "D2") (pin "AJ22") (pinfunction "GND_AJ22") (pintype "bidirectional"))
      (node (ref "D2") (pin "AJ7") (pinfunction "GND_AJ7") (pintype "bidirectional"))
      (node (ref "D5") (pin "11") (pinfunction "EP_11") (pintype "power_in"))
      (node (ref "D5") (pin "4") (pinfunction "PGND_4") (pintype "power_in"))
      (node (ref "D5") (pin "8") (pinfunction "GND_8") (pintype "power_in"))
      (node (ref "R190") (pin "1") (pinfunction "+_1") (pintype "passive"))
      (node (ref "R47") (pin "2") (pinfunction "-_2") (pintype "passive"))
      (node (ref "R48") (pin "2") (pinfunction "-_2") (pintype "passive"))
      (node (ref "R57") (pin "2") (pinfunction "-_2") (pintype "passive"))
      (node (ref "R59") (pin "1") (pinfunction "+_1") (pintype "passive"))
      (node (ref "U1") (pin "A9") (pinfunction "VSS_A9") (pintype "power_in"))
      (node (ref "U1") (pin "B1") (pinfunction "VSSQ_B1") (pintype "power_in"))
      (node (ref "U1") (pin "B3") (pinfunction "VSS_B3") (pintype "power_in"))
      (node (ref "U1") (pin "B9") (pinfunction "VSSQ_B9") (pintype "power_in"))
      (node (ref "U1") (pin "D1") (pinfunction "VSSQ_D1") (pintype "power_in"))
      (node (ref "U1") (pin "D8") (pinfunction "VSSQ_D8") (pintype "power_in"))
      (node (ref "U1") (pin "E1") (pinfunction "VSS_E1") (pintype "power_in"))
      (node (ref "U1") (pin "E2") (pinfunction "VSSQ_E2") (pintype "power_in"))
      (node (ref "U1") (pin "E8") (pinfunction "VSSQ_E8") (pintype "power_in"))
      (node (ref "U1") (pin "F9") (pinfunction "VSSQ_F9") (pintype "power_in"))
      (node (ref "U1") (pin "G1") (pinfunction "VSSQ_G1") (pintype "power_in"))
      (node (ref "U1") (pin "G8") (pinfunction "VSS_G8") (pintype "power_in"))
      (node (ref "U1") (pin "G9") (pinfunction "VSSQ_G9") (pintype "power_in"))
      (node (ref "U1") (pin "J2") (pinfunction "VSS_J2") (pintype "power_in"))
      (node (ref "U1") (pin "J8") (pinfunction "VSS_J8") (pintype "power_in"))
      (node (ref "U1") (pin "M1") (pinfunction "VSS_M1") (pintype "power_in"))
      (node (ref "U1") (pin "M9") (pinfunction "VSS_M9") (pintype "power_in"))
      (node (ref "U1") (pin "P1") (pinfunction "VSS_P1") (pintype "power_in"))
      (node (ref "U1") (pin "P9") (pinfunction "VSS_P9") (pintype "power_in"))
      (node (ref "U1") (pin "T1") (pinfunction "VSS_T1") (pintype "power_in"))
      (node (ref "U1") (pin "T9") (pinfunction "VSS_T9") (pintype "power_in"))
      (node (ref "U2") (pin "A9") (pinfunction "VSS_A9") (pintype "power_in"))
      (node (ref "U2") (pin "B1") (pinfunction "VSSQ_B1") (pintype "power_in"))
      (node (ref "U2") (pin "B3") (pinfunction "VSS_B3") (pintype "power_in"))
      (node (ref "U2") (pin "B9") (pinfunction "VSSQ_B9") (pintype "power_in"))
      (node (ref "U2") (pin "D1") (pinfunction "VSSQ_D1") (pintype "power_in"))
      (node (ref "U2") (pin "D8") (pinfunction "VSSQ_D8") (pintype "power_in"))
      (node (ref "U2") (pin "E1") (pinfunction "VSS_E1") (pintype "power_in"))
      (node (ref "U2") (pin "E2") (pinfunction "VSSQ_E2") (pintype "power_in"))
      (node (ref "U2") (pin "E8") (pinfunction "VSSQ_E8") (pintype "power_in"))
      (node (ref "U2") (pin "F9") (pinfunction "VSSQ_F9") (pintype "power_in"))
      (node (ref "U2") (pin "G1") (pinfunction "VSSQ_G1") (pintype "power_in"))
      (node (ref "U2") (pin "G8") (pinfunction "VSS_G8") (pintype "power_in"))
      (node (ref "U2") (pin "G9") (pinfunction "VSSQ_G9") (pintype "power_in"))
      (node (ref "U2") (pin "J2") (pinfunction "VSS_J2") (pintype "power_in"))
      (node (ref "U2") (pin "J8") (pinfunction "VSS_J8") (pintype "power_in"))
      (node (ref "U2") (pin "M1") (pinfunction "VSS_M1") (pintype "power_in"))
      (node (ref "U2") (pin "M9") (pinfunction "VSS_M9") (pintype "power_in"))
      (node (ref "U2") (pin "P1") (pinfunction "VSS_P1") (pintype "power_in"))
      (node (ref "U2") (pin "P9") (pinfunction "VSS_P9") (pintype "power_in"))
      (node (ref "U2") (pin "T1") (pinfunction "VSS_T1") (pintype "power_in"))
      (node (ref "U2") (pin "T9") (pinfunction "VSS_T9") (pintype "power_in"))
    )
    (net (code "90") (name "Net-(C20-+)") (class "Default")
      (node (ref "C20") (pin "1") (pinfunction "+_1") (pintype "passive"))
      (node (ref "D5") (pin "1") (pinfunction "REFIN_1") (pintype "input"))
      (node (ref "R58") (pin "2") (pinfunction "-_2") (pintype "passive"))
      (node (ref "R59") (pin "2") (pinfunction "-_2") (pintype "passive"))
    )
    (net (code "91") (name "Net-(D2C-RZQ_0)") (class "Default")
      (node (ref "D2") (pin "AG17") (pinfunction "RZQ_0_AG17") (pintype "bidirectional"))
      (node (ref "R57") (pin "1") (pinfunction "+_1") (pintype "passive"))
    )
    (net (code "92") (name "Net-(D5-EN)") (class "Default")
      (node (ref "D5") (pin "7") (pinfunction "EN_7") (pintype "input"))
      (node (ref "R56") (pin "2") (pinfunction "-_2") (pintype "passive"))
    )
    (net (code "93") (name "Net-(D5-PGOOD)") (class "Default")
      (node (ref "D5") (pin "9") (pinfunction "PGOOD_9") (pintype "open_collector"))
      (node (ref "R55") (pin "2") (pinfunction "-_2") (pintype "passive"))
    )
    (net (code "94") (name "Net-(R47-+)") (class "Default")
      (node (ref "R47") (pin "1") (pinfunction "+_1") (pintype "passive"))
      (node (ref "U1") (pin "L8") (pinfunction "ZQ_L8") (pintype "input"))
    )
    (net (code "95") (name "Net-(R48-+)") (class "Default")
      (node (ref "R48") (pin "1") (pinfunction "+_1") (pintype "passive"))
      (node (ref "U2") (pin "L8") (pinfunction "ZQ_L8") (pintype "input"))
    )
    (net (code "96") (name "VCC1P5_DDR3") (class "Default")
      (node (ref "C19") (pin "1") (pinfunction "+_1") (pintype "passive"))
      (node (ref "D5") (pin "2") (pinfunction "VLDOIN_2") (pintype "power_in"))
      (node (ref "R49") (pin "1") (pinfunction "+_1") (pintype "passive"))
      (node (ref "R58") (pin "1") (pinfunction "+_1") (pintype "passive"))
      (node (ref "U1") (pin "A1") (pinfunction "VDDQ_A1") (pintype "power_in"))
      (node (ref "U1") (pin "A8") (pinfunction "VDDQ_A8") (pintype "power_in"))
      (node (ref "U1") (pin "B2") (pinfunction "VDD_B2") (pintype "power_in"))
      (node (ref "U1") (pin "C1") (pinfunction "VDDQ_C1") (pintype "power_in"))
      (node (ref "U1") (pin "C9") (pinfunction "VDDQ_C9") (pintype "power_in"))
      (node (ref "U1") (pin "D2") (pinfunction "VDDQ_D2") (pintype "power_in"))
      (node (ref "U1") (pin "D9") (pinfunction "VDD_D9") (pintype "power_in"))
      (node (ref "U1") (pin "E9") (pinfunction "VDDQ_E9") (pintype "power_in"))
      (node (ref "U1") (pin "F1") (pinfunction "VDDQ_F1") (pintype "power_in"))
      (node (ref "U1") (pin "G7") (pinfunction "VDD_G7") (pintype "power_in"))
      (node (ref "U1") (pin "H2") (pinfunction "VDDQ_H2") (pintype "power_in"))
      (node (ref "U1") (pin "H9") (pinfunction "VDDQ_H9") (pintype "power_in"))
      (node (ref "U1") (pin "K2") (pinfunction "VDD_K2") (pintype "power_in"))
      (node (ref "U1") (pin "K8") (pinfunction "VDD_K8") (pintype "power_in"))
      (node (ref "U1") (pin "N1") (pinfunction "VDD_N1") (pintype "power_in"))
      (node (ref "U1") (pin "N9") (pinfunction "VDD_N9") (pintype "power_in"))
      (node (ref "U1") (pin "R1") (pinfunction "VDD_R1") (pintype "power_in"))
      (node (ref "U1") (pin "R9") (pinfunction "VDD_R9") (pintype "power_in"))
      (node (ref "U2") (pin "A1") (pinfunction "VDDQ_A1") (pintype "power_in"))
      (node (ref "U2") (pin "A8") (pinfunction "VDDQ_A8") (pintype "power_in"))
      (node (ref "U2") (pin "B2") (pinfunction "VDD_B2") (pintype "power_in"))
      (node (ref "U2") (pin "C1") (pinfunction "VDDQ_C1") (pintype "power_in"))
      (node (ref "U2") (pin "C9") (pinfunction "VDDQ_C9") (pintype "power_in"))
      (node (ref "U2") (pin "D2") (pinfunction "VDDQ_D2") (pintype "power_in"))
      (node (ref "U2") (pin "D9") (pinfunction "VDD_D9") (pintype "power_in"))
      (node (ref "U2") (pin "E9") (pinfunction "VDDQ_E9") (pintype "power_in"))
      (node (ref "U2") (pin "F1") (pinfunction "VDDQ_F1") (pintype "power_in"))
      (node (ref "U2") (pin "G7") (pinfunction "VDD_G7") (pintype "power_in"))
      (node (ref "U2") (pin "H2") (pinfunction "VDDQ_H2") (pintype "power_in"))
      (node (ref "U2") (pin "H9") (pinfunction "VDDQ_H9") (pintype "power_in"))
      (node (ref "U2") (pin "K2") (pinfunction "VDD_K2") (pintype "power_in"))
      (node (ref "U2") (pin "K8") (pinfunction "VDD_K8") (pintype "power_in"))
      (node (ref "U2") (pin "N1") (pinfunction "VDD_N1") (pintype "power_in"))
      (node (ref "U2") (pin "N9") (pinfunction "VDD_N9") (pintype "power_in"))
      (node (ref "U2") (pin "R1") (pinfunction "VDD_R1") (pintype "power_in"))
      (node (ref "U2") (pin "R9") (pinfunction "VDD_R9") (pintype "power_in"))
    )
    (net (code "97") (name "VCC3P3") (class "Default")
      (node (ref "C16") (pin "1") (pinfunction "+_1") (pintype "passive"))
      (node (ref "D5") (pin "10") (pinfunction "VIN_10") (pintype "power_in"))
      (node (ref "R55") (pin "1") (pinfunction "+_1") (pintype "passive"))
      (node (ref "R56") (pin "1") (pinfunction "+_1") (pintype "passive"))
    )
    (net (code "98") (name "unconnected-(D2B-CLK1n-PadY16)") (class "Default")
      (node (ref "D2") (pin "Y16") (pinfunction "CLK1n_Y16") (pintype "bidirectional"))
    )
    (net (code "99") (name "unconnected-(D2B-DIFFIO_RX_B18n-PadAG11)") (class "Default")
      (node (ref "D2") (pin "AG11") (pinfunction "DIFFIO_RX_B18n_AG11") (pintype "bidirectional"))
    )
    (net (code "100") (name "unconnected-(D2B-DIFFIO_TX_B17n-PadAH9)") (class "Default")
      (node (ref "D2") (pin "AH9") (pinfunction "DIFFIO_TX_B17n_AH9") (pintype "bidirectional+no_connect"))
    )
    (net (code "101") (name "unconnected-(D2B-DIFFIO_TX_B17p-PadAG10)") (class "Default")
      (node (ref "D2") (pin "AG10") (pinfunction "DIFFIO_TX_B17p_AG10") (pintype "bidirectional+no_connect"))
    )
    (net (code "102") (name "unconnected-(D2B-DIFFIO_TX_B20n-PadAK3)") (class "Default")
      (node (ref "D2") (pin "AK3") (pinfunction "DIFFIO_TX_B20n_AK3") (pintype "bidirectional+no_connect"))
    )
    (net (code "103") (name "unconnected-(D2B-DIFFIO_TX_B20p-PadAK2)") (class "Default")
      (node (ref "D2") (pin "AK2") (pinfunction "DIFFIO_TX_B20p_AK2") (pintype "bidirectional+no_connect"))
    )
    (net (code "104") (name "unconnected-(D2B-DIFFIO_TX_B21n-PadAK4)") (class "Default")
      (node (ref "D2") (pin "AK4") (pinfunction "DIFFIO_TX_B21n_AK4") (pintype "bidirectional+no_connect"))
    )
    (net (code "105") (name "unconnected-(D2B-DIFFIO_TX_B21p-PadAJ4)") (class "Default")
      (node (ref "D2") (pin "AJ4") (pinfunction "DIFFIO_TX_B21p_AJ4") (pintype "bidirectional+no_connect"))
    )
    (net (code "106") (name "unconnected-(D2B-DIFFIO_TX_B24n-PadAK6)") (class "Default")
      (node (ref "D2") (pin "AK6") (pinfunction "DIFFIO_TX_B24n_AK6") (pintype "bidirectional+no_connect"))
    )
    (net (code "107") (name "unconnected-(D2B-DIFFIO_TX_B24p-PadAJ5)") (class "Default")
      (node (ref "D2") (pin "AJ5") (pinfunction "DIFFIO_TX_B24p_AJ5") (pintype "bidirectional+no_connect"))
    )
    (net (code "108") (name "unconnected-(D2B-IO-PadAC14)") (class "Default")
      (node (ref "D2") (pin "AC14") (pinfunction "IO_AC14") (pintype "bidirectional+no_connect"))
    )
    (net (code "109") (name "unconnected-(D2B-IO-PadAG13)") (class "Default")
      (node (ref "D2") (pin "AG13") (pinfunction "IO_AG13") (pintype "bidirectional+no_connect"))
    )
    (net (code "110") (name "unconnected-(D2C-CLK2n-PadAB17)") (class "Default")
      (node (ref "D2") (pin "AB17") (pinfunction "CLK2n_AB17") (pintype "bidirectional"))
    )
    (net (code "111") (name "unconnected-(D2C-CLK3n-PadAD17)") (class "Default")
      (node (ref "D2") (pin "AD17") (pinfunction "CLK3n_AD17") (pintype "bidirectional"))
    )
    (net (code "112") (name "unconnected-(D2C-CLK3p-PadAC18)") (class "Default")
      (node (ref "D2") (pin "AC18") (pinfunction "CLK3p_AC18") (pintype "bidirectional"))
    )
    (net (code "113") (name "unconnected-(D2C-DIFFIO_RX_B74n-PadAD21)") (class "Default")
      (node (ref "D2") (pin "AD21") (pinfunction "DIFFIO_RX_B74n_AD21") (pintype "bidirectional+no_connect"))
    )
    (net (code "114") (name "unconnected-(D2C-DIFFIO_RX_B74p-PadAD20)") (class "Default")
      (node (ref "D2") (pin "AD20") (pinfunction "DIFFIO_RX_B74p_AD20") (pintype "bidirectional+no_connect"))
    )
    (net (code "115") (name "unconnected-(D2C-DIFFIO_RX_B75n-PadAA20)") (class "Default")
      (node (ref "D2") (pin "AA20") (pinfunction "DIFFIO_RX_B75n_AA20") (pintype "bidirectional+no_connect"))
    )
    (net (code "116") (name "unconnected-(D2C-DIFFIO_RX_B75p-PadY19)") (class "Default")
      (node (ref "D2") (pin "Y19") (pinfunction "DIFFIO_RX_B75p_Y19") (pintype "bidirectional+no_connect"))
    )
    (net (code "117") (name "unconnected-(D2C-DIFFIO_RX_B78n-PadAC23)") (class "Default")
      (node (ref "D2") (pin "AC23") (pinfunction "DIFFIO_RX_B78n_AC23") (pintype "bidirectional+no_connect"))
    )
    (net (code "118") (name "unconnected-(D2C-DIFFIO_RX_B78p-PadAC22)") (class "Default")
      (node (ref "D2") (pin "AC22") (pinfunction "DIFFIO_RX_B78p_AC22") (pintype "bidirectional+no_connect"))
    )
    (net (code "119") (name "unconnected-(D2C-DIFFIO_TX_B80n-PadAE24)") (class "Default")
      (node (ref "D2") (pin "AE24") (pinfunction "DIFFIO_TX_B80n_AE24") (pintype "bidirectional+no_connect"))
    )
    (net (code "120") (name "unconnected-(D2C-DIFFIO_TX_B80p-PadAD24)") (class "Default")
      (node (ref "D2") (pin "AD24") (pinfunction "DIFFIO_TX_B80p_AD24") (pintype "bidirectional+no_connect"))
    )
    (net (code "121") (name "unconnected-(D2C-GND-PadAA19)") (class "Default")
      (node (ref "D2") (pin "AA19") (pinfunction "GND_AA19") (pintype "bidirectional"))
    )
    (net (code "122") (name "unconnected-(D2C-GND-PadAA21)") (class "Default")
      (node (ref "D2") (pin "AA21") (pinfunction "GND_AA21") (pintype "bidirectional"))
    )
    (net (code "123") (name "unconnected-(D2C-GND-PadAB21)") (class "Default")
      (node (ref "D2") (pin "AB21") (pinfunction "GND_AB21") (pintype "bidirectional"))
    )
    (net (code "124") (name "unconnected-(D2C-GND-PadAF26)") (class "Default")
      (node (ref "D2") (pin "AF26") (pinfunction "GND_AF26") (pintype "bidirectional"))
    )
    (net (code "125") (name "unconnected-(D2C-GND-PadAG26)") (class "Default")
      (node (ref "D2") (pin "AG26") (pinfunction "GND_AG26") (pintype "bidirectional"))
    )
    (net (code "126") (name "unconnected-(D2C-GND-PadAH19)") (class "Default")
      (node (ref "D2") (pin "AH19") (pinfunction "GND_AH19") (pintype "bidirectional"))
    )
    (net (code "127") (name "unconnected-(D2C-GND-PadAH22)") (class "Default")
      (node (ref "D2") (pin "AH22") (pinfunction "GND_AH22") (pintype "bidirectional"))
    )
    (net (code "128") (name "unconnected-(D2C-GND-PadAH25)") (class "Default")
      (node (ref "D2") (pin "AH25") (pinfunction "GND_AH25") (pintype "bidirectional"))
    )
    (net (code "129") (name "unconnected-(D2C-GND-PadAJ25)") (class "Default")
      (node (ref "D2") (pin "AJ25") (pinfunction "GND_AJ25") (pintype "bidirectional"))
    )
    (net (code "130") (name "unconnected-(D2C-GND-PadAJ26)") (class "Default")
      (node (ref "D2") (pin "AJ26") (pinfunction "GND_AJ26") (pintype "bidirectional"))
    )
    (net (code "131") (name "unconnected-(D2C-GND-PadAK29)") (class "Default")
      (node (ref "D2") (pin "AK29") (pinfunction "GND_AK29") (pintype "bidirectional"))
    )
    (net (code "132") (name "unconnected-(D2C-GND-PadV18)") (class "Default")
      (node (ref "D2") (pin "V18") (pinfunction "GND_V18") (pintype "bidirectional"))
    )
    (net (code "133") (name "unconnected-(D2C-GND-PadW19)") (class "Default")
      (node (ref "D2") (pin "W19") (pinfunction "GND_W19") (pintype "bidirectional"))
    )
    (net (code "134") (name "unconnected-(D2C-GND-PadY18)") (class "Default")
      (node (ref "D2") (pin "Y18") (pinfunction "GND_Y18") (pintype "bidirectional"))
    )
    (net (code "135") (name "unconnected-(D2C-IO-PadAF25)") (class "Default")
      (node (ref "D2") (pin "AF25") (pinfunction "IO_AF25") (pintype "bidirectional+no_connect"))
    )
    (net (code "136") (name "unconnected-(D2C-IO-PadAH27)") (class "Default")
      (node (ref "D2") (pin "AH27") (pinfunction "IO_AH27") (pintype "bidirectional+no_connect"))
    )
    (net (code "137") (name "unconnected-(D2C-IO-PadAJ19)") (class "Default")
      (node (ref "D2") (pin "AJ19") (pinfunction "IO_AJ19") (pintype "bidirectional+no_connect"))
    )
    (net (code "138") (name "unconnected-(D2C-IO-PadAK16)") (class "Default")
      (node (ref "D2") (pin "AK16") (pinfunction "IO_AK16") (pintype "bidirectional+no_connect"))
    )
    (net (code "139") (name "unconnected-(D2C-IO-PadAK28)") (class "Default")
      (node (ref "D2") (pin "AK28") (pinfunction "IO_AK28") (pintype "bidirectional+no_connect"))
    )
    (net (code "140") (name "unconnected-(U1C-NC-PadJ1)") (class "Default")
      (node (ref "U1") (pin "J1") (pinfunction "NC_J1") (pintype "passive"))
    )
    (net (code "141") (name "unconnected-(U1C-NC-PadJ9)") (class "Default")
      (node (ref "U1") (pin "J9") (pinfunction "NC_J9") (pintype "passive"))
    )
    (net (code "142") (name "unconnected-(U1C-NC-PadL1)") (class "Default")
      (node (ref "U1") (pin "L1") (pinfunction "NC_L1") (pintype "passive"))
    )
    (net (code "143") (name "unconnected-(U1C-NC-PadL9)") (class "Default")
      (node (ref "U1") (pin "L9") (pinfunction "NC_L9") (pintype "passive"))
    )
    (net (code "144") (name "unconnected-(U1C-NC-PadM7)") (class "Default")
      (node (ref "U1") (pin "M7") (pinfunction "NC_M7") (pintype "passive"))
    )
    (net (code "145") (name "unconnected-(U2C-NC-PadJ1)") (class "Default")
      (node (ref "U2") (pin "J1") (pinfunction "NC_J1") (pintype "passive"))
    )
    (net (code "146") (name "unconnected-(U2C-NC-PadJ9)") (class "Default")
      (node (ref "U2") (pin "J9") (pinfunction "NC_J9") (pintype "passive"))
    )
    (net (code "147") (name "unconnected-(U2C-NC-PadL1)") (class "Default")
      (node (ref "U2") (pin "L1") (pinfunction "NC_L1") (pintype "passive"))
    )
    (net (code "148") (name "unconnected-(U2C-NC-PadL9)") (class "Default")
      (node (ref "U2") (pin "L9") (pinfunction "NC_L9") (pintype "passive"))
    )
    (net (code "149") (name "unconnected-(U2C-NC-PadM7)") (class "Default")
      (node (ref "U2") (pin "M7") (pinfunction "NC_M7") (pintype "passive"))
    )
  )
)
